# moisture_meter.net
KiCad netlist of a schematic drawn in EAGLE
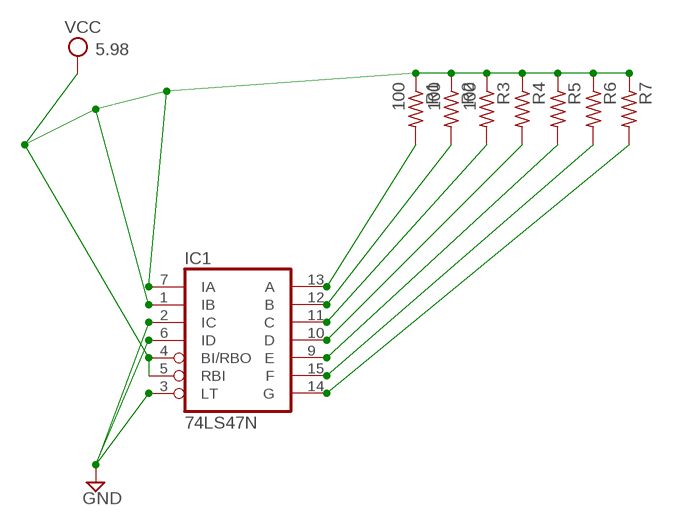
[diagram p0: schematic, sheet 1]

(export (version "E")
  (design (tool "Eeschema 10.0.6"))
  (components
    (comp (ref "IC1")
      (value "74LS47N")
      (footprint "eagle-import:DIL16")
      (libsource (lib "eagle-import") (part "7447NLS"))
    )
    (comp (ref "R1")
      (value "100")
      (footprint "eagle-import:0207_10")
      (libsource (lib "eagle-import") (part "R-US_0207/10"))
    )
    (comp (ref "R2")
      (value "100")
      (footprint "eagle-import:0207_10")
      (libsource (lib "eagle-import") (part "R-US_0207/10"))
    )
    (comp (ref "R3")
      (value "100")
      (footprint "eagle-import:0207_10")
      (libsource (lib "eagle-import") (part "R-US_0207/10"))
    )
    (comp (ref "R4")
      (value "R-US_0207/10")
      (footprint "eagle-import:0207_10")
      (libsource (lib "eagle-import") (part "R-US_0207/10"))
    )
    (comp (ref "R5")
      (value "R-US_0207/10")
      (footprint "eagle-import:0207_10")
      (libsource (lib "eagle-import") (part "R-US_0207/10"))
    )
    (comp (ref "R6")
      (value "R-US_0207/10")
      (footprint "eagle-import:0207_10")
      (libsource (lib "eagle-import") (part "R-US_0207/10"))
    )
    (comp (ref "R7")
      (value "R-US_0207/10")
      (footprint "eagle-import:0207_10")
      (libsource (lib "eagle-import") (part "R-US_0207/10"))
    )
  )
  (nets
    (net (code "1") (name "GND") (class "Default")
      (node (ref "IC1") (pin "2") (pinfunction "IC_2") (pintype "input"))
      (node (ref "IC1") (pin "3") (pinfunction "LT_3") (pintype "input"))
      (node (ref "IC1") (pin "6") (pinfunction "ID_6") (pintype "input"))
    )
    (net (code "2") (name "Net-(IC1A-A)") (class "Default")
      (node (ref "IC1") (pin "13") (pinfunction "A_13") (pintype "output"))
      (node (ref "R1") (pin "2") (pinfunction "2_2") (pintype "passive"))
    )
    (net (code "3") (name "Net-(IC1A-B)") (class "Default")
      (node (ref "IC1") (pin "12") (pinfunction "B_12") (pintype "output"))
      (node (ref "R2") (pin "2") (pinfunction "2_2") (pintype "passive"))
    )
    (net (code "4") (name "Net-(IC1A-C)") (class "Default")
      (node (ref "IC1") (pin "11") (pinfunction "C_11") (pintype "output"))
      (node (ref "R3") (pin "2") (pinfunction "2_2") (pintype "passive"))
    )
    (net (code "5") (name "Net-(IC1A-D)") (class "Default")
      (node (ref "IC1") (pin "10") (pinfunction "D_10") (pintype "output"))
      (node (ref "R4") (pin "2") (pinfunction "2_2") (pintype "passive"))
    )
    (net (code "6") (name "Net-(IC1A-E)") (class "Default")
      (node (ref "IC1") (pin "9") (pinfunction "E_9") (pintype "output"))
      (node (ref "R5") (pin "2") (pinfunction "2_2") (pintype "passive"))
    )
    (net (code "7") (name "Net-(IC1A-F)") (class "Default")
      (node (ref "IC1") (pin "15") (pinfunction "F_15") (pintype "output"))
      (node (ref "R6") (pin "2") (pinfunction "2_2") (pintype "passive"))
    )
    (net (code "8") (name "Net-(IC1A-G)") (class "Default")
      (node (ref "IC1") (pin "14") (pinfunction "G_14") (pintype "output"))
      (node (ref "R7") (pin "2") (pinfunction "2_2") (pintype "passive"))
    )
    (net (code "9") (name "VCC") (class "Default")
      (node (ref "IC1") (pin "1") (pinfunction "IB_1") (pintype "input"))
      (node (ref "IC1") (pin "4") (pinfunction "BI/RBO_4") (pintype "input"))
      (node (ref "IC1") (pin "5") (pinfunction "RBI_5") (pintype "input"))
      (node (ref "IC1") (pin "7") (pinfunction "IA_7") (pintype "input"))
      (node (ref "R1") (pin "1") (pinfunction "1_1") (pintype "passive"))
      (node (ref "R2") (pin "1") (pinfunction "1_1") (pintype "passive"))
      (node (ref "R3") (pin "1") (pinfunction "1_1") (pintype "passive"))
      (node (ref "R4") (pin "1") (pinfunction "1_1") (pintype "passive"))
      (node (ref "R5") (pin "1") (pinfunction "1_1") (pintype "passive"))
      (node (ref "R6") (pin "1") (pinfunction "1_1") (pintype "passive"))
      (node (ref "R7") (pin "1") (pinfunction "1_1") (pintype "passive"))
    )
  )
)
